# SenseSing-prog-adaptor-v0_1.net
KiCad netlist of a schematic drawn in EAGLE
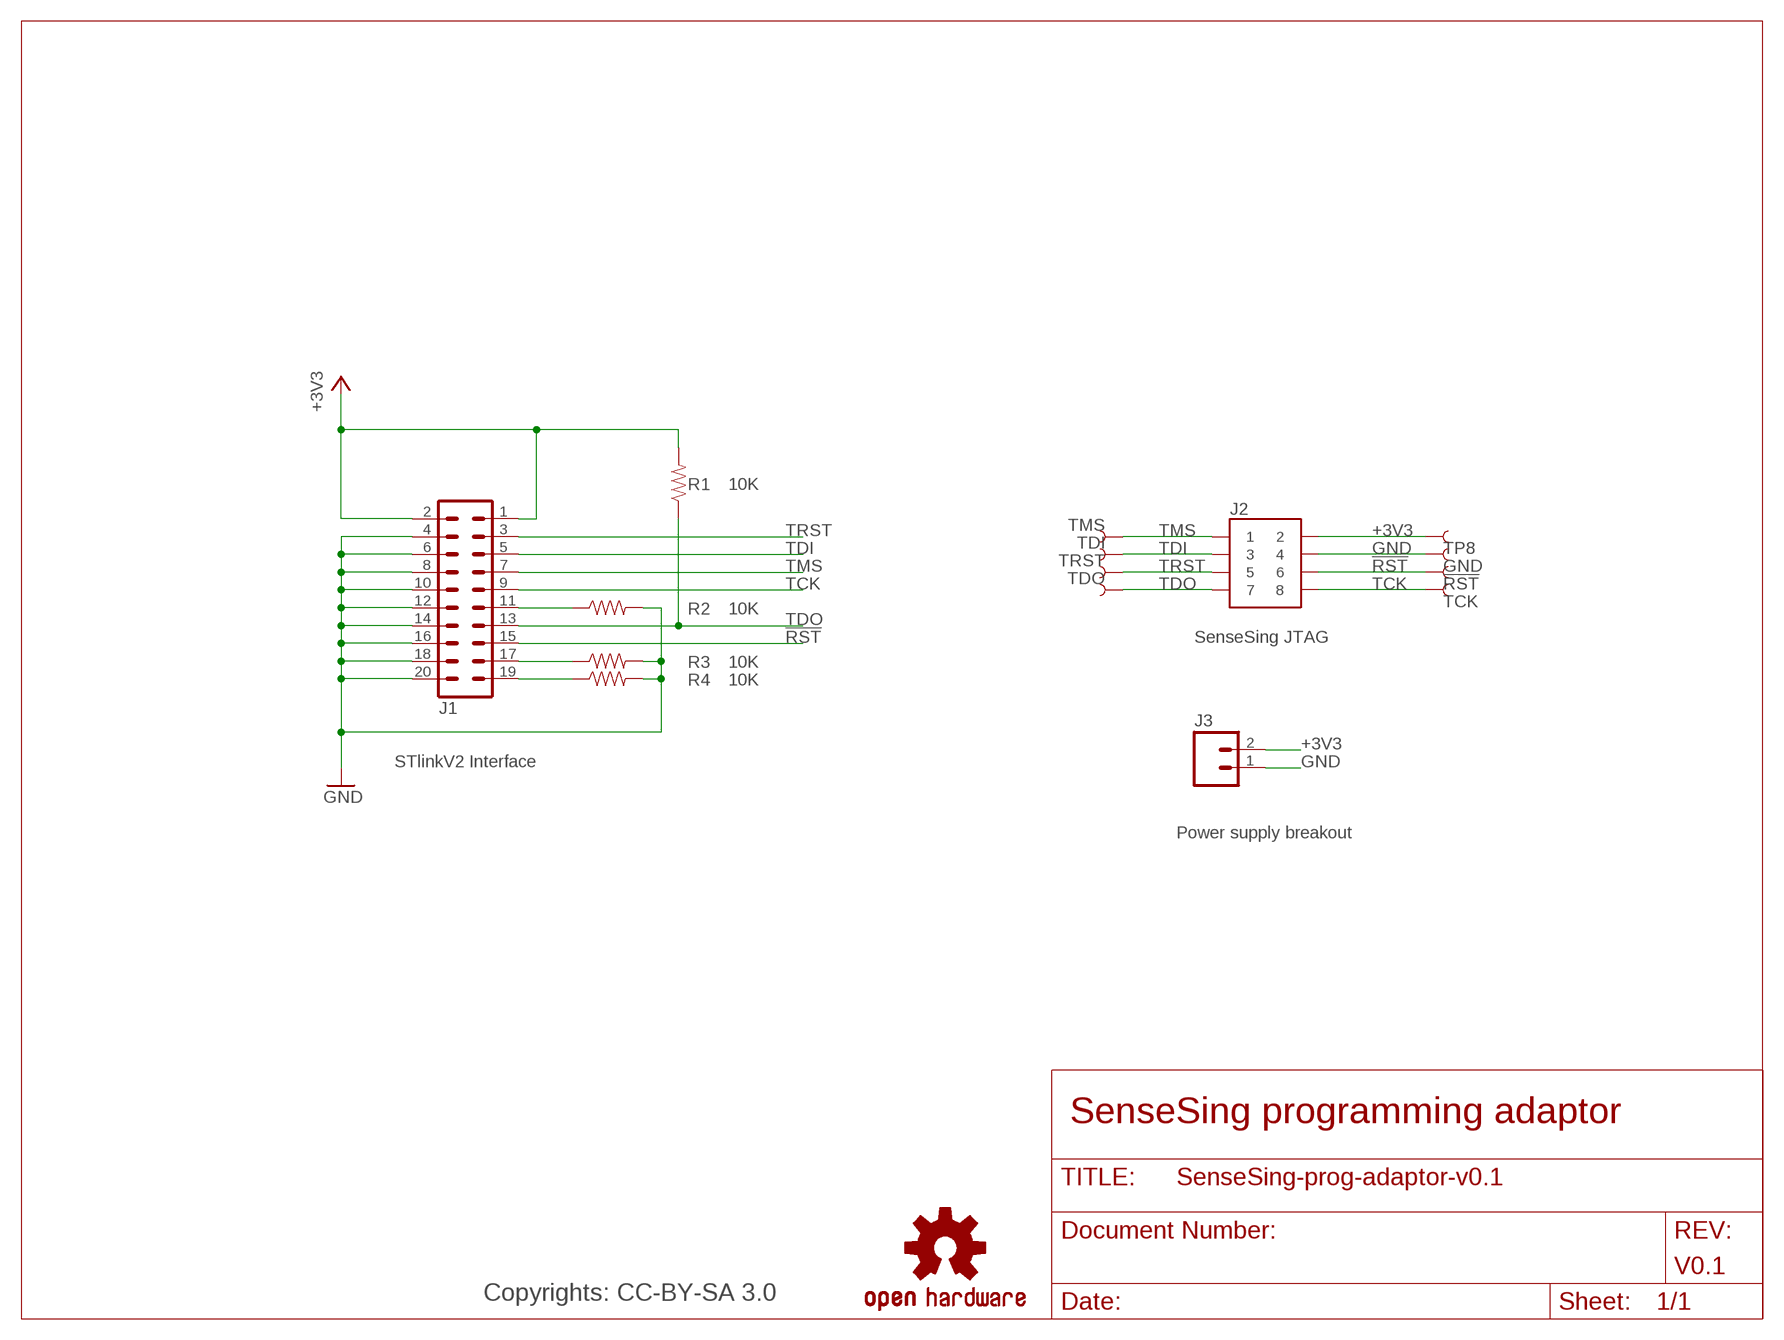
[diagram p0: schematic, sheet 1]

(export (version "E")
  (design (tool "Eeschema 10.0.6"))
  (components
    (comp (ref "!RST")
      (value "TEST-POINT3")
      (footprint "eagle-import:PAD.03X.03")
      (libsource (lib "eagle-import") (part "TEST-POINT3"))
    )
    (comp (ref "GND")
      (value "TEST-POINT3")
      (footprint "eagle-import:PAD.03X.03")
      (libsource (lib "eagle-import") (part "TEST-POINT3"))
    )
    (comp (ref "J1")
      (value "ML20")
      (footprint "eagle-import:ML20")
      (libsource (lib "eagle-import") (part "ML20"))
    )
    (comp (ref "J2")
      (value "JTAG_CONNECTOR")
      (footprint "eagle-import:JTAG_DIP")
      (libsource (lib "eagle-import") (part "JTAG_CONNECTOR"))
    )
    (comp (ref "J3")
      (value "M02PTH")
      (footprint "eagle-import:1X02")
      (libsource (lib "eagle-import") (part "M02PTH"))
    )
    (comp (ref "LOGO1")
      (value "OSHW-LOGOPAD")
      (footprint "eagle-import:OSHW-LOGO-M-PAD")
      (libsource (lib "eagle-import") (part "OSHW-LOGOPAD"))
    )
    (comp (ref "R1")
      (value "10K")
      (footprint "eagle-import:AXIAL-0.3")
      (libsource (lib "eagle-import") (part "RESISTORAXIAL-0.3"))
    )
    (comp (ref "R2")
      (value "10K")
      (footprint "eagle-import:AXIAL-0.3")
      (libsource (lib "eagle-import") (part "RESISTORAXIAL-0.3"))
    )
    (comp (ref "R3")
      (value "10K")
      (footprint "eagle-import:AXIAL-0.3")
      (libsource (lib "eagle-import") (part "RESISTORAXIAL-0.3"))
    )
    (comp (ref "R4")
      (value "10K")
      (footprint "eagle-import:AXIAL-0.3")
      (libsource (lib "eagle-import") (part "RESISTORAXIAL-0.3"))
    )
    (comp (ref "TCK")
      (value "TEST-POINT3")
      (footprint "eagle-import:PAD.03X.03")
      (libsource (lib "eagle-import") (part "TEST-POINT3"))
    )
    (comp (ref "TDI")
      (value "TEST-POINT3")
      (footprint "eagle-import:PAD.03X.03")
      (libsource (lib "eagle-import") (part "TEST-POINT3"))
    )
    (comp (ref "TDO")
      (value "TEST-POINT3")
      (footprint "eagle-import:PAD.03X.03")
      (libsource (lib "eagle-import") (part "TEST-POINT3"))
    )
    (comp (ref "TMS")
      (value "TEST-POINT3")
      (footprint "eagle-import:PAD.03X.03")
      (libsource (lib "eagle-import") (part "TEST-POINT3"))
    )
    (comp (ref "TP8")
      (value "TEST-POINT3")
      (footprint "eagle-import:PAD.03X.03")
      (libsource (lib "eagle-import") (part "TEST-POINT3"))
    )
    (comp (ref "TRST")
      (value "TEST-POINT3")
      (footprint "eagle-import:PAD.03X.03")
      (libsource (lib "eagle-import") (part "TEST-POINT3"))
    )
  )
  (nets
    (net (code "1") (name "+3V3") (class "Default")
      (node (ref "J1") (pin "1") (pinfunction "1_1") (pintype "passive"))
      (node (ref "J1") (pin "2") (pinfunction "2_2") (pintype "passive"))
      (node (ref "J2") (pin "2") (pinfunction "2_2") (pintype "bidirectional"))
      (node (ref "J3") (pin "2") (pinfunction "2_2") (pintype "passive"))
      (node (ref "R1") (pin "P$2") (pinfunction "2_P$2") (pintype "passive"))
      (node (ref "TP8") (pin "P$1") (pinfunction "1_P$1") (pintype "bidirectional"))
    )
    (net (code "2") (name "/TCK") (class "Default")
      (node (ref "J1") (pin "9") (pinfunction "9_9") (pintype "passive"))
      (node (ref "J2") (pin "8") (pinfunction "8_8") (pintype "bidirectional"))
      (node (ref "TCK") (pin "P$1") (pinfunction "1_P$1") (pintype "bidirectional"))
    )
    (net (code "3") (name "/TDI") (class "Default")
      (node (ref "J1") (pin "5") (pinfunction "5_5") (pintype "passive"))
      (node (ref "J2") (pin "3") (pinfunction "3_3") (pintype "bidirectional"))
      (node (ref "TDI") (pin "P$1") (pinfunction "1_P$1") (pintype "bidirectional"))
    )
    (net (code "4") (name "/TDO") (class "Default")
      (node (ref "J1") (pin "13") (pinfunction "13_13") (pintype "passive"))
      (node (ref "J2") (pin "7") (pinfunction "7_7") (pintype "bidirectional"))
      (node (ref "R1") (pin "P$1") (pinfunction "1_P$1") (pintype "passive"))
      (node (ref "TDO") (pin "P$1") (pinfunction "1_P$1") (pintype "bidirectional"))
    )
    (net (code "5") (name "/TMS") (class "Default")
      (node (ref "J1") (pin "7") (pinfunction "7_7") (pintype "passive"))
      (node (ref "J2") (pin "1") (pinfunction "1_1") (pintype "bidirectional"))
      (node (ref "TMS") (pin "P$1") (pinfunction "1_P$1") (pintype "bidirectional"))
    )
    (net (code "6") (name "/TRST") (class "Default")
      (node (ref "J1") (pin "3") (pinfunction "3_3") (pintype "passive"))
      (node (ref "J2") (pin "5") (pinfunction "5_5") (pintype "bidirectional"))
      (node (ref "TRST") (pin "P$1") (pinfunction "1_P$1") (pintype "bidirectional"))
    )
    (net (code "7") (name "/~{RST}") (class "Default")
      (node (ref "!RST") (pin "P$1") (pinfunction "1_P$1") (pintype "bidirectional"))
      (node (ref "J1") (pin "15") (pinfunction "15_15") (pintype "passive"))
      (node (ref "J2") (pin "6") (pinfunction "6_6") (pintype "bidirectional"))
    )
    (net (code "8") (name "GND") (class "Default")
      (node (ref "GND") (pin "P$1") (pinfunction "1_P$1") (pintype "bidirectional"))
      (node (ref "J1") (pin "10") (pinfunction "10_10") (pintype "passive"))
      (node (ref "J1") (pin "12") (pinfunction "12_12") (pintype "passive"))
      (node (ref "J1") (pin "14") (pinfunction "14_14") (pintype "passive"))
      (node (ref "J1") (pin "16") (pinfunction "16_16") (pintype "passive"))
      (node (ref "J1") (pin "18") (pinfunction "18_18") (pintype "passive"))
      (node (ref "J1") (pin "20") (pinfunction "20_20") (pintype "passive"))
      (node (ref "J1") (pin "4") (pinfunction "4_4") (pintype "passive"))
      (node (ref "J1") (pin "6") (pinfunction "6_6") (pintype "passive"))
      (node (ref "J1") (pin "8") (pinfunction "8_8") (pintype "passive"))
      (node (ref "J2") (pin "4") (pinfunction "4_4") (pintype "bidirectional"))
      (node (ref "J3") (pin "1") (pinfunction "1_1") (pintype "passive"))
      (node (ref "R2") (pin "P$2") (pinfunction "2_P$2") (pintype "passive"))
      (node (ref "R3") (pin "P$2") (pinfunction "2_P$2") (pintype "passive"))
      (node (ref "R4") (pin "P$2") (pinfunction "2_P$2") (pintype "passive"))
    )
    (net (code "9") (name "Net-(R2-1)") (class "Default")
      (node (ref "J1") (pin "11") (pinfunction "11_11") (pintype "passive"))
      (node (ref "R2") (pin "P$1") (pinfunction "1_P$1") (pintype "passive"))
    )
    (net (code "10") (name "Net-(R3-1)") (class "Default")
      (node (ref "J1") (pin "17") (pinfunction "17_17") (pintype "passive"))
      (node (ref "R3") (pin "P$1") (pinfunction "1_P$1") (pintype "passive"))
    )
    (net (code "11") (name "Net-(R4-1)") (class "Default")
      (node (ref "J1") (pin "19") (pinfunction "19_19") (pintype "passive"))
      (node (ref "R4") (pin "P$1") (pinfunction "1_P$1") (pintype "passive"))
    )
  )
)
